# SLAVE.net
KiCad netlist of a schematic drawn in Altium Designer
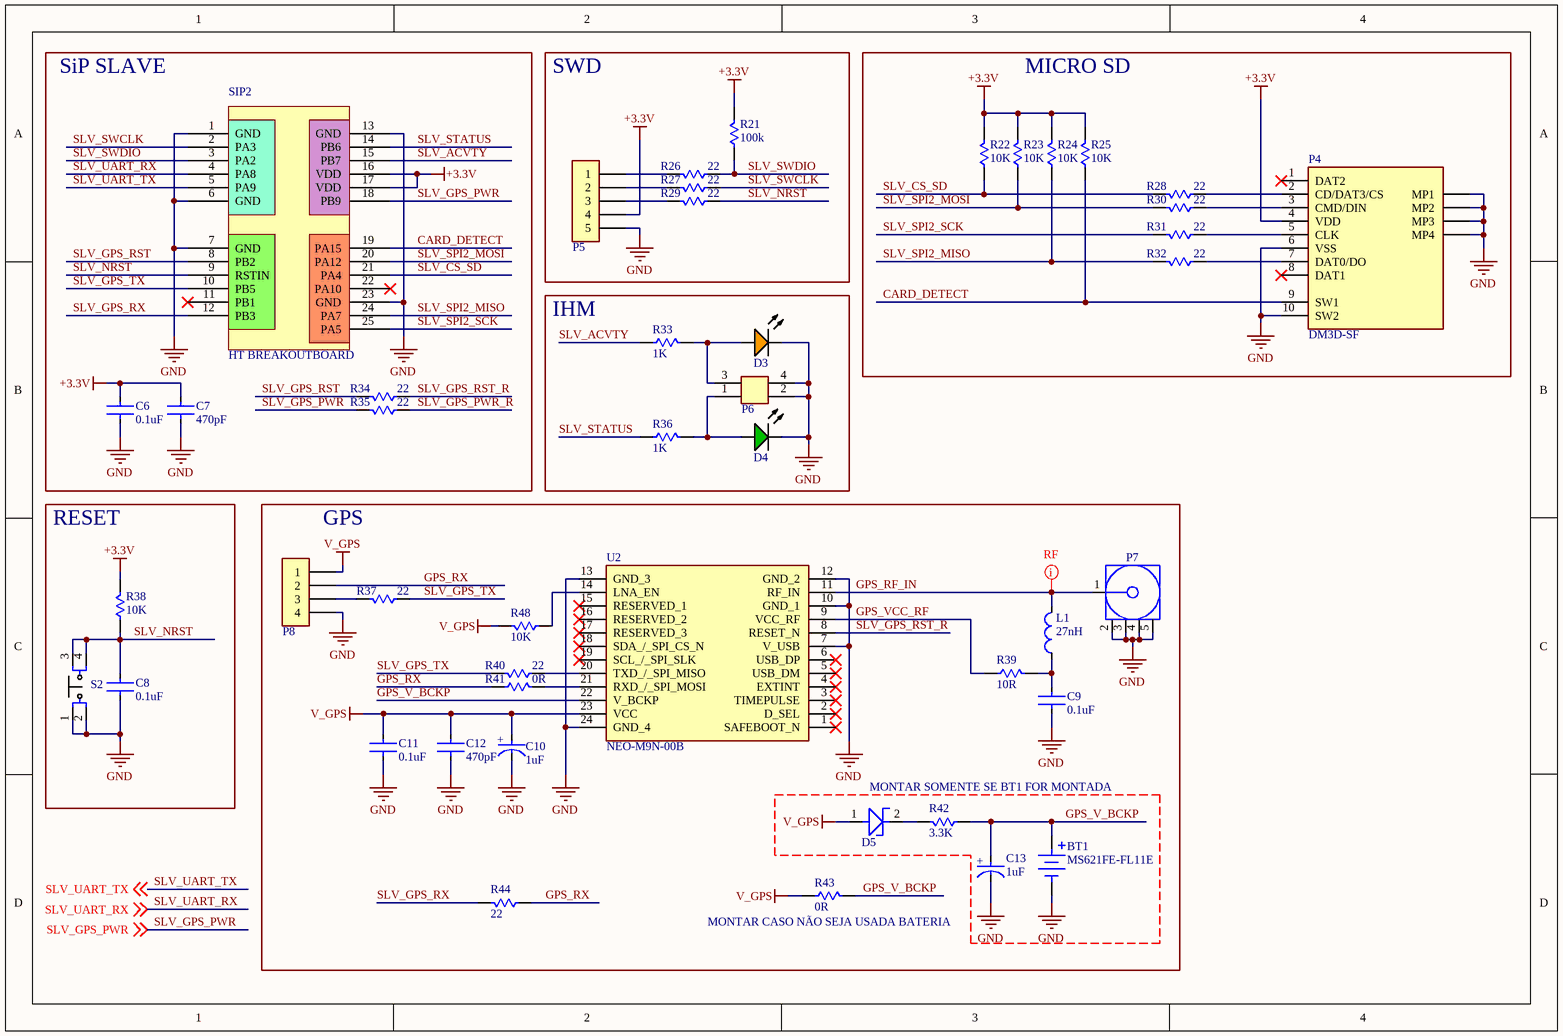
[diagram p0: SLAVE.SchDoc]

(export (version "E")
  (design (tool "Eeschema 10.0.6"))
  (components
    (comp (ref "BT1")
      (value "MS621FE-FL11E")
      (footprint "BAT_MS621FE-FL11E")
      (description "MS621FE-FL11E Coin Cell, Lithium, 5.5MAH, 3V Rechargeable Rohs")
      (fields (field (name "MANUFACTURER") "Seiko") (field (name "VOLTAGE") "3V"))
      (libsource (lib "Battery") (part "MS621FE-FL11E"))
    )
    (comp (ref "C6")
      (value "0.1uF")
      (footprint "0805-CAP")
      (description "CAP CER SMD 0805, 0.1uF / 16V, ±10%")
      (fields
        (field (name "MANUFACTURER") "Yageo")
        (field (name "MANUFACTURER PART NUMBER") "AC0805KRX7R7BB104")
      )
      (libsource (lib "Capacitor") (part "AC0805KRX7R7BB104"))
    )
    (comp (ref "C7")
      (value "470pF")
      (footprint "0805-CAP")
      (description "CAP CER SMD 0805, 470pF / 100V, ±5% C0G/NP0")
      (fields
        (field (name "MANUFACTURER") "Wurth Electronics")
        (field (name "MANUFACTURER PART NUMBER") "885012007086")
      )
      (libsource (lib "Capacitor") (part "885012007086"))
    )
    (comp (ref "C8")
      (value "0.1uF")
      (footprint "0805-CAP")
      (description "CAP CER SMD 0805, 0.1uF / 16V, ±10%")
      (fields
        (field (name "MANUFACTURER") "Yageo")
        (field (name "MANUFACTURER PART NUMBER") "AC0805KRX7R7BB104")
      )
      (libsource (lib "Capacitor") (part "AC0805KRX7R7BB104"))
    )
    (comp (ref "C9")
      (value "0.1uF")
      (footprint "0805-CAP")
      (description "CAP CER SMD 0805, 0.1uF / 16V, ±10%")
      (fields
        (field (name "MANUFACTURER") "Yageo")
        (field (name "MANUFACTURER PART NUMBER") "AC0805KRX7R7BB104")
      )
      (libsource (lib "Capacitor") (part "AC0805KRX7R7BB104"))
    )
    (comp (ref "C10")
      (value "1uF")
      (footprint "1206-CAP-TANT")
      (description "CAP TANT SMD 1206, 1uF / 20V, ±10%")
      (fields
        (field (name "MANUFACTURER") "Kyocera AVX")
        (field (name "MANUFACTURER PART NUMBER") "TAJA105K020RNJ")
      )
      (libsource (lib "Capacitor") (part "TAJA105K020RNJ"))
    )
    (comp (ref "C11")
      (value "0.1uF")
      (footprint "0805-CAP")
      (description "CAP CER SMD 0805, 0.1uF / 16V, ±10%")
      (fields
        (field (name "MANUFACTURER") "Yageo")
        (field (name "MANUFACTURER PART NUMBER") "AC0805KRX7R7BB104")
      )
      (libsource (lib "Capacitor") (part "AC0805KRX7R7BB104"))
    )
    (comp (ref "C12")
      (value "470pF")
      (footprint "0805-CAP")
      (description "CAP CER SMD 0805, 470pF / 100V, ±5% C0G/NP0")
      (fields
        (field (name "MANUFACTURER") "Wurth Electronics")
        (field (name "MANUFACTURER PART NUMBER") "885012007086")
      )
      (libsource (lib "Capacitor") (part "885012007086"))
    )
    (comp (ref "C13")
      (value "1uF")
      (footprint "1206-CAP-TANT")
      (description "CAP TANT SMD 1206, 1uF / 20V, ±10%")
      (fields
        (field (name "MANUFACTURER") "Kyocera AVX")
        (field (name "MANUFACTURER PART NUMBER") "TAJA105K020RNJ")
      )
      (libsource (lib "Capacitor") (part "TAJA105K020RNJ"))
    )
    (comp (ref "D3")
      (value "ORANGE")
      (footprint "0805-LED-ORANGE")
      (description "LED ORANGE, SMD 0805, 2.1V/30mA")
      (fields
        (field (name "MANUFACTURER") "Vishay Lite-On")
        (field (name "MANUFACTURER PART NUMBER") "LTST-C170AKT")
      )
      (libsource (lib "Diode") (part "LTST-C170AKT"))
    )
    (comp (ref "D4")
      (value "GREEN")
      (footprint "0805-LED-GREEN")
      (description "LED GREEN, SMD 0805, 2.1V/30mA")
      (fields
        (field (name "MANUFACTURER") "Vishay Lite-On")
        (field (name "MANUFACTURER PART NUMBER") "LTST-C170GKT")
      )
      (libsource (lib "Diode") (part "LTST-C170GKT"))
    )
    (comp (ref "D5")
      (value "NRVB120VLSFT1G")
      (footprint "SOD-123")
      (description "DIODE SHOTTKY SMD SOD-123F, 0,3V/1A, VBR 20V")
      (fields (field (name "MANUFACTURER") "ON Semiconductor"))
      (libsource (lib "Diode") (part "NRVB120VLSFT1G"))
    )
    (comp (ref "L1")
      (value "27nH")
      (footprint "PE-0603CD270JTT")
      (description "Inductor RF Chip Wirewound 27nH 5% 250MHz 35Q-Factor Ceramic 600mA 220mOhm DCR 0603 T/R")
      (fields
        (field (name "MANUFACTURER") "Pulse")
        (field (name "MANUFACTURER PART NUMBER") "PE-0603CD270JTT")
      )
      (libsource (lib "Inductor") (part "PE-0603CD270JTT"))
    )
    (comp (ref "P4")
      (value "DM3D-SF")
      (footprint "DM3DSF")
      (description "Memory Card Connectors MICRO SD CD CONN STD SMT PUSHPULL")
      (fields (field (name "MANUFACTURER") "Hirose"))
      (libsource (lib "Connector") (part "DM3D-SF"))
    )
    (comp (ref "P5")
      (value "Header 6")
      (footprint "_HEADER_5P_PVF")
      (fields
        (field (name "MANUFACTURER") "Amphenol ICC / FCI")
        (field (name "MANUFACTURER PART NUMBER") "75915-305LF")
      )
      (libsource (lib "Connector") (part "75915-305LF"))
    )
    (comp (ref "P6")
      (value "_HEADER_2X2_PVM_2.54MM")
      (footprint "67997-404HLF")
      (description "HEADER 2X3, PTH-2.54MM, VERT, MALE")
      (libsource (lib "Connector") (part "_HEADER_2X2_PVM_2.54MM"))
    )
    (comp (ref "P7")
      (value "CON-SMA-EDGE-S")
      (footprint "CON-SMA-EDGE-S")
      (description "Sma Female Connector, Pcb Edge Mount Rohs Compliant: Yes")
      (fields (field (name "MANUFACTURER") "RF Solutions"))
      (libsource (lib "Connector") (part "CON-SMA-EDGE-S"))
    )
    (comp (ref "P8")
      (value "NEO-5M-MODULE-WITHOUT-PPS")
      (footprint "NEO-5M-MODULE-NO-PPS")
      (description "NEO 5M GPS MODULE (NO PPS SIGNAL)")
      (libsource (lib "Connector") (part "NEO-5M-MODULE-WITHOUT-PPS"))
    )
    (comp (ref "R21")
      (value "100k")
      (footprint "0805-RES")
      (description "RES SMD 0805, 100K OHM 5% 1/8W")
      (fields
        (field (name "MANUFACTURER") "Panasonic")
        (field (name "MANUFACTURER PART NUMBER") "ERJ-6GEYJ104V")
      )
      (libsource (lib "Resistor") (part "ERJ-6GEYJ104V"))
    )
    (comp (ref "R22")
      (value "10K")
      (footprint "0805-RES")
      (description "Res Thin Film 0805 10K Ohm 1% 1/4W ±100ppm/°C Molded SMD Paper T/R")
      (fields
        (field (name "MANUFACTURER") "Stackpole Electronics")
        (field (name "MANUFACTURER PART NUMBER") "RNCP0805FTD10K0")
      )
      (libsource (lib "Resistor") (part "RNCP0805FTD10K0"))
    )
    (comp (ref "R23")
      (value "10K")
      (footprint "0805-RES")
      (description "Res Thin Film 0805 10K Ohm 1% 1/4W ±100ppm/°C Molded SMD Paper T/R")
      (fields
        (field (name "MANUFACTURER") "Stackpole Electronics")
        (field (name "MANUFACTURER PART NUMBER") "RNCP0805FTD10K0")
      )
      (libsource (lib "Resistor") (part "RNCP0805FTD10K0"))
    )
    (comp (ref "R24")
      (value "10K")
      (footprint "0805-RES")
      (description "Res Thin Film 0805 10K Ohm 1% 1/4W ±100ppm/°C Molded SMD Paper T/R")
      (fields
        (field (name "MANUFACTURER") "Stackpole Electronics")
        (field (name "MANUFACTURER PART NUMBER") "RNCP0805FTD10K0")
      )
      (libsource (lib "Resistor") (part "RNCP0805FTD10K0"))
    )
    (comp (ref "R25")
      (value "10K")
      (footprint "0805-RES")
      (description "Res Thin Film 0805 10K Ohm 1% 1/4W ±100ppm/°C Molded SMD Paper T/R")
      (fields
        (field (name "MANUFACTURER") "Stackpole Electronics")
        (field (name "MANUFACTURER PART NUMBER") "RNCP0805FTD10K0")
      )
      (libsource (lib "Resistor") (part "RNCP0805FTD10K0"))
    )
    (comp (ref "R26")
      (value "22")
      (footprint "0805-RES")
      (description "RES SMD 0805, 22 OHM 5% 1/4W")
      (fields
        (field (name "MANUFACTURER") "Panasonic")
        (field (name "MANUFACTURER PART NUMBER") "ERJ-P06J220V")
      )
      (libsource (lib "Resistor") (part "ERJ-P06J220V"))
    )
    (comp (ref "R27")
      (value "22")
      (footprint "0805-RES")
      (description "RES SMD 0805, 22 OHM 5% 1/4W")
      (fields
        (field (name "MANUFACTURER") "Panasonic")
        (field (name "MANUFACTURER PART NUMBER") "ERJ-P06J220V")
      )
      (libsource (lib "Resistor") (part "ERJ-P06J220V"))
    )
    (comp (ref "R28")
      (value "22")
      (footprint "0805-RES")
      (description "RES SMD 0805, 22 OHM 5% 1/4W")
      (fields
        (field (name "MANUFACTURER") "Panasonic")
        (field (name "MANUFACTURER PART NUMBER") "ERJ-P06J220V")
      )
      (libsource (lib "Resistor") (part "ERJ-P06J220V"))
    )
    (comp (ref "R29")
      (value "22")
      (footprint "0805-RES")
      (description "RES SMD 0805, 22 OHM 5% 1/4W")
      (fields
        (field (name "MANUFACTURER") "Panasonic")
        (field (name "MANUFACTURER PART NUMBER") "ERJ-P06J220V")
      )
      (libsource (lib "Resistor") (part "ERJ-P06J220V"))
    )
    (comp (ref "R30")
      (value "22")
      (footprint "0805-RES")
      (description "RES SMD 0805, 22 OHM 5% 1/4W")
      (fields
        (field (name "MANUFACTURER") "Panasonic")
        (field (name "MANUFACTURER PART NUMBER") "ERJ-P06J220V")
      )
      (libsource (lib "Resistor") (part "ERJ-P06J220V"))
    )
    (comp (ref "R31")
      (value "22")
      (footprint "0805-RES")
      (description "RES SMD 0805, 22 OHM 5% 1/4W")
      (fields
        (field (name "MANUFACTURER") "Panasonic")
        (field (name "MANUFACTURER PART NUMBER") "ERJ-P06J220V")
      )
      (libsource (lib "Resistor") (part "ERJ-P06J220V"))
    )
    (comp (ref "R32")
      (value "22")
      (footprint "0805-RES")
      (description "RES SMD 0805, 22 OHM 5% 1/4W")
      (fields
        (field (name "MANUFACTURER") "Panasonic")
        (field (name "MANUFACTURER PART NUMBER") "ERJ-P06J220V")
      )
      (libsource (lib "Resistor") (part "ERJ-P06J220V"))
    )
    (comp (ref "R33")
      (value "1K")
      (footprint "0805-RES")
      (description "Res Thin Film 0805 1K Ohm 1% 0.25W(1/4W) ±100ppm/C Sulfur Resistant Pad SMD T/R")
      (fields
        (field (name "MANUFACTURER") "Stackpole Electronics")
        (field (name "MANUFACTURER PART NUMBER") "RNCP0805FTD1K00")
      )
      (libsource (lib "Resistor") (part "RNCP0805FTD1K00"))
    )
    (comp (ref "R34")
      (value "22")
      (footprint "0805-RES")
      (description "RES SMD 0805, 22 OHM 5% 1/4W")
      (fields
        (field (name "MANUFACTURER") "Panasonic")
        (field (name "MANUFACTURER PART NUMBER") "ERJ-P06J220V")
      )
      (libsource (lib "Resistor") (part "ERJ-P06J220V"))
    )
    (comp (ref "R35")
      (value "22")
      (footprint "0805-RES")
      (description "RES SMD 0805, 22 OHM 5% 1/4W")
      (fields
        (field (name "MANUFACTURER") "Panasonic")
        (field (name "MANUFACTURER PART NUMBER") "ERJ-P06J220V")
      )
      (libsource (lib "Resistor") (part "ERJ-P06J220V"))
    )
    (comp (ref "R36")
      (value "1K")
      (footprint "0805-RES")
      (description "Res Thin Film 0805 1K Ohm 1% 0.25W(1/4W) ±100ppm/C Sulfur Resistant Pad SMD T/R")
      (fields
        (field (name "MANUFACTURER") "Stackpole Electronics")
        (field (name "MANUFACTURER PART NUMBER") "RNCP0805FTD1K00")
      )
      (libsource (lib "Resistor") (part "RNCP0805FTD1K00"))
    )
    (comp (ref "R37")
      (value "22")
      (footprint "0805-RES")
      (description "RES SMD 0805, 22 OHM 5% 1/4W")
      (fields
        (field (name "MANUFACTURER") "Panasonic")
        (field (name "MANUFACTURER PART NUMBER") "ERJ-P06J220V")
      )
      (libsource (lib "Resistor") (part "ERJ-P06J220V"))
    )
    (comp (ref "R38")
      (value "10K")
      (footprint "0805-RES")
      (description "Res Thin Film 0805 10K Ohm 1% 1/4W ±100ppm/°C Molded SMD Paper T/R")
      (fields
        (field (name "MANUFACTURER") "Stackpole Electronics")
        (field (name "MANUFACTURER PART NUMBER") "RNCP0805FTD10K0")
      )
      (libsource (lib "Resistor") (part "RNCP0805FTD10K0"))
    )
    (comp (ref "R39")
      (value "10R")
      (footprint "0805-RES")
      (description "RES SMD 0805, 10 OHM 1% 1/3W")
      (fields
        (field (name "MANUFACTURER") "Vishay")
        (field (name "MANUFACTURER PART NUMBER") "CRCW080510R0FKEAHP")
      )
      (libsource (lib "Resistor") (part "CRCW080510R0FKEAHP"))
    )
    (comp (ref "R40")
      (value "22")
      (footprint "0805-RES")
      (description "RES SMD 0805, 22 OHM 5% 1/4W")
      (fields
        (field (name "MANUFACTURER") "Panasonic")
        (field (name "MANUFACTURER PART NUMBER") "ERJ-P06J220V")
      )
      (libsource (lib "Resistor") (part "ERJ-P06J220V"))
    )
    (comp (ref "R41")
      (value "0R")
      (footprint "0805-RES")
      (description "RES SMD 0805, 0 OHM JUMPER 1/8W")
      (fields (field (name "TOLERANCE") "5%") (field (name "MANUFACTURER PART NUMBER") "RC0805JR-070RL"))
      (libsource (lib "Resistor") (part "RC0805JR-070RL"))
    )
    (comp (ref "R42")
      (value "3.3K")
      (footprint "0805-RES")
      (description "RES SMD 0805, 3.3K OHM 5% 0.4W")
      (fields (field (name "MANUFACTURER") "Rohm") (field (name "MANUFACTURER PART NUMBER") "ESR10EZPJ332"))
      (libsource (lib "Resistor") (part "ESR10EZPJ332"))
    )
    (comp (ref "R43")
      (value "0R")
      (footprint "0805-RES")
      (description "RES SMD 0805, 0 OHM JUMPER 1/8W")
      (fields (field (name "TOLERANCE") "5%") (field (name "MANUFACTURER PART NUMBER") "RC0805JR-070RL"))
      (libsource (lib "Resistor") (part "RC0805JR-070RL"))
    )
    (comp (ref "R44")
      (value "22")
      (footprint "0805-RES")
      (description "RES SMD 0805, 22 OHM 5% 1/4W")
      (fields
        (field (name "MANUFACTURER") "Panasonic")
        (field (name "MANUFACTURER PART NUMBER") "ERJ-P06J220V")
      )
      (libsource (lib "Resistor") (part "ERJ-P06J220V"))
    )
    (comp (ref "R48")
      (value "10K")
      (footprint "0805-RES")
      (description "Res Thin Film 0805 10K Ohm 1% 1/4W ±100ppm/°C Molded SMD Paper T/R")
      (fields
        (field (name "MANUFACTURER") "Stackpole Electronics")
        (field (name "MANUFACTURER PART NUMBER") "RNCP0805FTD10K0")
      )
      (libsource (lib "Resistor") (part "RNCP0805FTD10K0"))
    )
    (comp (ref "S2")
      (value "EVQ-P7A01P")
      (footprint "EVQP7A")
      (description "Switch Tactile N.O. SPST Rectangular Button Gull Wing 0.05A 12VDC 2.2N SMD Embossed T/R")
      (fields (field (name "MANUFACTURER") "Panasonic"))
      (libsource (lib "Switches") (part "EVQ-P7A01P"))
    )
    (comp (ref "SIP2")
      (value "HT BREAKOUTBOARD")
      (footprint "HT BREAKOUTBOARD PINS")
      (description "Pinos Fêmea para encaixe de HT Breakout")
      (libsource (lib "Connector") (part "HT BREAKOUTBOARD"))
    )
    (comp (ref "U2")
      (value "NEO-M9N-00B")
      (footprint "NEO-M9N-00B-MFG")
      (description "GNSS module, Flash, TCXO, SAW, LNA, LCC, 12x16 mm Professional Grade")
      (fields (field (name "MANUFACTURER") "u-blox"))
      (libsource (lib "IC") (part "NEO-M9N-00B"))
    )
  )
  (nets
    (net (code "1") (name "+3.3V") (class "Default")
      (node (ref "C6") (pin "1") (pinfunction "1_1") (pintype "passive"))
      (node (ref "C7") (pin "1") (pinfunction "1_1") (pintype "passive"))
      (node (ref "P4") (pin "4") (pinfunction "VDD_4") (pintype "passive"))
      (node (ref "P5") (pin "4") (pinfunction "4_4") (pintype "passive"))
      (node (ref "R21") (pin "2") (pinfunction "2_2") (pintype "passive"))
      (node (ref "R22") (pin "2") (pinfunction "2_2") (pintype "passive"))
      (node (ref "R23") (pin "2") (pinfunction "2_2") (pintype "passive"))
      (node (ref "R24") (pin "2") (pinfunction "2_2") (pintype "passive"))
      (node (ref "R25") (pin "2") (pinfunction "2_2") (pintype "passive"))
      (node (ref "R38") (pin "2") (pinfunction "2_2") (pintype "passive"))
      (node (ref "SIP2") (pin "16") (pinfunction "VDD_16") (pintype "passive"))
      (node (ref "SIP2") (pin "17") (pinfunction "VDD_17") (pintype "passive"))
    )
    (net (code "3") (name "/CARD_DETECT") (class "Default")
      (node (ref "P4") (pin "9") (pinfunction "SW1_9") (pintype "passive"))
      (node (ref "R25") (pin "1") (pinfunction "1_1") (pintype "passive"))
      (node (ref "SIP2") (pin "19") (pinfunction "PA15_19") (pintype "passive"))
    )
    (net (code "4") (name "/GPS_RF_IN") (class "Default")
      (node (ref "L1") (pin "2") (pinfunction "2_2") (pintype "passive"))
      (node (ref "P7") (pin "1") (pinfunction "SIGNAL_1") (pintype "passive"))
      (node (ref "U2") (pin "11") (pinfunction "RF_IN_11") (pintype "passive"))
    )
    (net (code "5") (name "/GPS_RX") (class "Default")
      (node (ref "P8") (pin "2") (pinfunction "2_2") (pintype "passive"))
      (node (ref "R41") (pin "1") (pinfunction "1_1") (pintype "passive"))
      (node (ref "R44") (pin "1") (pinfunction "1_1") (pintype "passive"))
    )
    (net (code "6") (name "/GPS_VCC_RF") (class "Default")
      (node (ref "R39") (pin "1") (pinfunction "1_1") (pintype "passive"))
      (node (ref "U2") (pin "9") (pinfunction "VCC_RF_9") (pintype "passive"))
    )
    (net (code "7") (name "/GPS_V_BCKP") (class "Default")
      (node (ref "BT1") (pin "POS") (pinfunction "POS_POS") (pintype "passive"))
      (node (ref "C13") (pin "1") (pinfunction "A_1") (pintype "passive"))
      (node (ref "R42") (pin "1") (pinfunction "1_1") (pintype "passive"))
      (node (ref "R43") (pin "2") (pinfunction "2_2") (pintype "passive"))
      (node (ref "U2") (pin "22") (pinfunction "V_BCKP_22") (pintype "passive"))
    )
    (net (code "8") (name "/SLV_ACVTY") (class "Default")
      (node (ref "R33") (pin "1") (pinfunction "1_1") (pintype "passive"))
      (node (ref "SIP2") (pin "15") (pinfunction "PB7_15") (pintype "passive"))
    )
    (net (code "9") (name "/SLV_CS_SD") (class "Default")
      (node (ref "R22") (pin "1") (pinfunction "1_1") (pintype "passive"))
      (node (ref "R28") (pin "2") (pinfunction "2_2") (pintype "passive"))
      (node (ref "SIP2") (pin "21") (pinfunction "PA4_21") (pintype "passive"))
    )
    (net (code "10") (name "/SLV_GPS_PWR_R") (class "Default")
      (node (ref "R35") (pin "1") (pinfunction "1_1") (pintype "passive"))
    )
    (net (code "11") (name "/SLV_GPS_RST") (class "Default")
      (node (ref "R34") (pin "2") (pinfunction "2_2") (pintype "passive"))
      (node (ref "SIP2") (pin "8") (pinfunction "PB2_8") (pintype "passive"))
    )
    (net (code "12") (name "/SLV_GPS_RST_R") (class "Default")
      (node (ref "R34") (pin "1") (pinfunction "1_1") (pintype "passive"))
      (node (ref "U2") (pin "8") (pinfunction "RESET_N_8") (pintype "passive"))
    )
    (net (code "13") (name "/SLV_GPS_RX") (class "Default")
      (node (ref "R44") (pin "2") (pinfunction "2_2") (pintype "passive"))
      (node (ref "SIP2") (pin "12") (pinfunction "PB3_12") (pintype "passive"))
    )
    (net (code "14") (name "/SLV_GPS_TX") (class "Default")
      (node (ref "R37") (pin "1") (pinfunction "1_1") (pintype "passive"))
      (node (ref "R40") (pin "2") (pinfunction "2_2") (pintype "passive"))
      (node (ref "SIP2") (pin "10") (pinfunction "PB5_10") (pintype "passive"))
    )
    (net (code "15") (name "/SLV_NRST") (class "Default")
      (node (ref "C8") (pin "1") (pinfunction "1_1") (pintype "passive"))
      (node (ref "R29") (pin "1") (pinfunction "1_1") (pintype "passive"))
      (node (ref "R38") (pin "1") (pinfunction "1_1") (pintype "passive"))
      (node (ref "S2") (pin "3") (pinfunction "3_3") (pintype "passive"))
      (node (ref "S2") (pin "4") (pinfunction "4_4") (pintype "passive"))
      (node (ref "SIP2") (pin "9") (pinfunction "RSTIN_9") (pintype "passive"))
    )
    (net (code "16") (name "/SLV_SPI2_MISO") (class "Default")
      (node (ref "R24") (pin "1") (pinfunction "1_1") (pintype "passive"))
      (node (ref "R32") (pin "2") (pinfunction "2_2") (pintype "passive"))
      (node (ref "SIP2") (pin "24") (pinfunction "PA7_24") (pintype "passive"))
    )
    (net (code "17") (name "/SLV_SPI2_MOSI") (class "Default")
      (node (ref "R23") (pin "1") (pinfunction "1_1") (pintype "passive"))
      (node (ref "R30") (pin "2") (pinfunction "2_2") (pintype "passive"))
      (node (ref "SIP2") (pin "20") (pinfunction "PA12_20") (pintype "passive"))
    )
    (net (code "18") (name "/SLV_SPI2_SCK") (class "Default")
      (node (ref "R31") (pin "2") (pinfunction "2_2") (pintype "passive"))
      (node (ref "SIP2") (pin "25") (pinfunction "PA5_25") (pintype "passive"))
    )
    (net (code "19") (name "/SLV_STATUS") (class "Default")
      (node (ref "R36") (pin "1") (pinfunction "1_1") (pintype "passive"))
      (node (ref "SIP2") (pin "14") (pinfunction "PB6_14") (pintype "passive"))
    )
    (net (code "20") (name "/SLV_SWCLK") (class "Default")
      (node (ref "R27") (pin "1") (pinfunction "1_1") (pintype "passive"))
      (node (ref "SIP2") (pin "2") (pinfunction "PA3_2") (pintype "passive"))
    )
    (net (code "21") (name "/SLV_SWDIO") (class "Default")
      (node (ref "R21") (pin "1") (pinfunction "1_1") (pintype "passive"))
      (node (ref "R26") (pin "1") (pinfunction "1_1") (pintype "passive"))
      (node (ref "SIP2") (pin "3") (pinfunction "PA2_3") (pintype "passive"))
    )
    (net (code "22") (name "GND") (class "Default")
      (node (ref "BT1") (pin "NEG") (pinfunction "NEG_NEG") (pintype "passive"))
      (node (ref "C10") (pin "2") (pinfunction "C_2") (pintype "passive"))
      (node (ref "C11") (pin "2") (pinfunction "2_2") (pintype "passive"))
      (node (ref "C12") (pin "2") (pinfunction "2_2") (pintype "passive"))
      (node (ref "C13") (pin "2") (pinfunction "C_2") (pintype "passive"))
      (node (ref "C6") (pin "2") (pinfunction "2_2") (pintype "passive"))
      (node (ref "C7") (pin "2") (pinfunction "2_2") (pintype "passive"))
      (node (ref "C8") (pin "2") (pinfunction "2_2") (pintype "passive"))
      (node (ref "C9") (pin "1") (pinfunction "1_1") (pintype "passive"))
      (node (ref "D3") (pin "2") (pinfunction "K_2") (pintype "passive"))
      (node (ref "D4") (pin "2") (pinfunction "K_2") (pintype "passive"))
      (node (ref "P4") (pin "10") (pinfunction "SW2_10") (pintype "passive"))
      (node (ref "P4") (pin "6") (pinfunction "VSS_6") (pintype "passive"))
      (node (ref "P4") (pin "MP1") (pinfunction "MP1_MP1") (pintype "passive"))
      (node (ref "P4") (pin "MP2") (pinfunction "MP2_MP2") (pintype "passive"))
      (node (ref "P4") (pin "MP3") (pinfunction "MP3_MP3") (pintype "passive"))
      (node (ref "P4") (pin "MP4") (pinfunction "MP4_MP4") (pintype "passive"))
      (node (ref "P5") (pin "5") (pinfunction "5_5") (pintype "passive"))
      (node (ref "P6") (pin "2") (pinfunction "2_2") (pintype "passive"))
      (node (ref "P6") (pin "4") (pinfunction "4_4") (pintype "passive"))
      (node (ref "P7") (pin "2") (pinfunction "GND1_2") (pintype "power_in"))
      (node (ref "P7") (pin "3") (pinfunction "GND2_3") (pintype "power_in"))
      (node (ref "P7") (pin "4") (pinfunction "GND3_4") (pintype "power_in"))
      (node (ref "P7") (pin "5") (pinfunction "GND4_5") (pintype "power_in"))
      (node (ref "P8") (pin "4") (pinfunction "4_4") (pintype "passive"))
      (node (ref "S2") (pin "1") (pinfunction "1_1") (pintype "passive"))
      (node (ref "S2") (pin "2") (pinfunction "2_2") (pintype "passive"))
      (node (ref "SIP2") (pin "1") (pinfunction "GND_1") (pintype "passive"))
      (node (ref "SIP2") (pin "13") (pinfunction "GND_13") (pintype "passive"))
      (node (ref "SIP2") (pin "23") (pinfunction "GND_23") (pintype "passive"))
      (node (ref "SIP2") (pin "6") (pinfunction "GND_6") (pintype "passive"))
      (node (ref "SIP2") (pin "7") (pinfunction "GND_7") (pintype "passive"))
      (node (ref "U2") (pin "10") (pinfunction "GND_1_10") (pintype "passive"))
      (node (ref "U2") (pin "12") (pinfunction "GND_2_12") (pintype "passive"))
      (node (ref "U2") (pin "13") (pinfunction "GND_3_13") (pintype "passive"))
      (node (ref "U2") (pin "24") (pinfunction "GND_4_24") (pintype "passive"))
      (node (ref "U2") (pin "7") (pinfunction "V_USB_7") (pintype "passive"))
    )
    (net (code "23") (name "Net-(C9-Pad2)") (class "Default")
      (node (ref "C9") (pin "2") (pinfunction "2_2") (pintype "passive"))
      (node (ref "L1") (pin "1") (pinfunction "1_1") (pintype "passive"))
      (node (ref "R39") (pin "2") (pinfunction "2_2") (pintype "passive"))
    )
    (net (code "24") (name "Net-(D3-A)") (class "Default")
      (node (ref "D3") (pin "1") (pinfunction "A_1") (pintype "passive"))
      (node (ref "P6") (pin "3") (pinfunction "3_3") (pintype "passive"))
      (node (ref "R33") (pin "2") (pinfunction "2_2") (pintype "passive"))
    )
    (net (code "25") (name "Net-(D4-A)") (class "Default")
      (node (ref "D4") (pin "1") (pinfunction "A_1") (pintype "passive"))
      (node (ref "P6") (pin "1") (pinfunction "1_1") (pintype "passive"))
      (node (ref "R36") (pin "2") (pinfunction "2_2") (pintype "passive"))
    )
    (net (code "26") (name "Net-(D5-Pad2)") (class "Default")
      (node (ref "D5") (pin "2") (pinfunction "2_2") (pintype "passive"))
      (node (ref "R42") (pin "2") (pinfunction "2_2") (pintype "passive"))
    )
    (net (code "27") (name "Net-(P4-CD{slash}DAT3{slash}CS)") (class "Default")
      (node (ref "P4") (pin "2") (pinfunction "CD/DAT3/CS_2") (pintype "passive"))
      (node (ref "R28") (pin "1") (pinfunction "1_1") (pintype "passive"))
    )
    (net (code "28") (name "Net-(P4-CLK)") (class "Default")
      (node (ref "P4") (pin "5") (pinfunction "CLK_5") (pintype "passive"))
      (node (ref "R31") (pin "1") (pinfunction "1_1") (pintype "passive"))
    )
    (net (code "29") (name "Net-(P4-CMD{slash}DIN)") (class "Default")
      (node (ref "P4") (pin "3") (pinfunction "CMD/DIN_3") (pintype "passive"))
      (node (ref "R30") (pin "1") (pinfunction "1_1") (pintype "passive"))
    )
    (net (code "30") (name "Net-(P4-DAT0{slash}DO)") (class "Default")
      (node (ref "P4") (pin "7") (pinfunction "DAT0/DO_7") (pintype "passive"))
      (node (ref "R32") (pin "1") (pinfunction "1_1") (pintype "passive"))
    )
    (net (code "31") (name "Net-(P5-Pad1)") (class "Default")
      (node (ref "P5") (pin "1") (pinfunction "1_1") (pintype "passive"))
      (node (ref "R26") (pin "2") (pinfunction "2_2") (pintype "passive"))
    )
    (net (code "32") (name "Net-(P5-Pad2)") (class "Default")
      (node (ref "P5") (pin "2") (pinfunction "2_2") (pintype "passive"))
      (node (ref "R27") (pin "2") (pinfunction "2_2") (pintype "passive"))
    )
    (net (code "33") (name "Net-(P5-Pad3)") (class "Default")
      (node (ref "P5") (pin "3") (pinfunction "3_3") (pintype "passive"))
      (node (ref "R29") (pin "2") (pinfunction "2_2") (pintype "passive"))
    )
    (net (code "34") (name "Net-(P8-Pad3)") (class "Default")
      (node (ref "P8") (pin "3") (pinfunction "3_3") (pintype "passive"))
      (node (ref "R37") (pin "2") (pinfunction "2_2") (pintype "passive"))
    )
    (net (code "35") (name "Net-(U2-LNA_EN)") (class "Default")
      (node (ref "R48") (pin "1") (pinfunction "1_1") (pintype "passive"))
      (node (ref "U2") (pin "14") (pinfunction "LNA_EN_14") (pintype "passive"))
    )
    (net (code "36") (name "Net-(U2-RXD_{slash}_SPI_MOSI)") (class "Default")
      (node (ref "R41") (pin "2") (pinfunction "2_2") (pintype "passive"))
      (node (ref "U2") (pin "21") (pinfunction "RXD_/_SPI_MOSI_21") (pintype "passive"))
    )
    (net (code "37") (name "Net-(U2-TXD_{slash}_SPI_MISO)") (class "Default")
      (node (ref "R40") (pin "1") (pinfunction "1_1") (pintype "passive"))
      (node (ref "U2") (pin "20") (pinfunction "TXD_/_SPI_MISO_20") (pintype "passive"))
    )
    (net (code "38") (name "SLV_GPS_PWR") (class "Default")
      (node (ref "R35") (pin "2") (pinfunction "2_2") (pintype "passive"))
      (node (ref "SIP2") (pin "18") (pinfunction "PB9_18") (pintype "passive"))
    )
    (net (code "39") (name "SLV_UART_RX") (class "Default")
      (node (ref "SIP2") (pin "4") (pinfunction "PA8_4") (pintype "passive"))
    )
    (net (code "40") (name "SLV_UART_TX") (class "Default")
      (node (ref "SIP2") (pin "5") (pinfunction "PA9_5") (pintype "passive"))
    )
    (net (code "41") (name "V_GPS") (class "Default")
      (node (ref "C10") (pin "1") (pinfunction "A_1") (pintype "passive"))
      (node (ref "C11") (pin "1") (pinfunction "1_1") (pintype "passive"))
      (node (ref "C12") (pin "1") (pinfunction "1_1") (pintype "passive"))
      (node (ref "D5") (pin "1") (pinfunction "1_1") (pintype "passive"))
      (node (ref "P8") (pin "1") (pinfunction "1_1") (pintype "passive"))
      (node (ref "R43") (pin "1") (pinfunction "1_1") (pintype "passive"))
      (node (ref "R48") (pin "2") (pinfunction "2_2") (pintype "passive"))
      (node (ref "U2") (pin "23") (pinfunction "VCC_23") (pintype "passive"))
    )
    (net (code "42") (name "unconnected-(P4-DAT1-Pad8)") (class "Default")
      (node (ref "P4") (pin "8") (pinfunction "DAT1_8") (pintype "passive+no_connect"))
    )
    (net (code "43") (name "unconnected-(P4-DAT2-Pad1)") (class "Default")
      (node (ref "P4") (pin "1") (pinfunction "DAT2_1") (pintype "passive+no_connect"))
    )
    (net (code "44") (name "unconnected-(SIP2-PA10-Pad22)") (class "Default")
      (node (ref "SIP2") (pin "22") (pinfunction "PA10_22") (pintype "passive+no_connect"))
    )
    (net (code "45") (name "unconnected-(SIP2-PB1-Pad11)") (class "Default")
      (node (ref "SIP2") (pin "11") (pinfunction "PB1_11") (pintype "passive+no_connect"))
    )
    (net (code "46") (name "unconnected-(U2-D_SEL-Pad2)") (class "Default")
      (node (ref "U2") (pin "2") (pinfunction "D_SEL_2") (pintype "passive+no_connect"))
    )
    (net (code "47") (name "unconnected-(U2-EXTINT-Pad4)") (class "Default")
      (node (ref "U2") (pin "4") (pinfunction "EXTINT_4") (pintype "passive+no_connect"))
    )
    (net (code "48") (name "unconnected-(U2-RESERVED_1-Pad15)") (class "Default")
      (node (ref "U2") (pin "15") (pinfunction "RESERVED_1_15") (pintype "passive+no_connect"))
    )
    (net (code "49") (name "unconnected-(U2-RESERVED_2-Pad16)") (class "Default")
      (node (ref "U2") (pin "16") (pinfunction "RESERVED_2_16") (pintype "passive+no_connect"))
    )
    (net (code "50") (name "unconnected-(U2-RESERVED_3-Pad17)") (class "Default")
      (node (ref "U2") (pin "17") (pinfunction "RESERVED_3_17") (pintype "passive+no_connect"))
    )
    (net (code "51") (name "unconnected-(U2-SAFEBOOT_N-Pad1)") (class "Default")
      (node (ref "U2") (pin "1") (pinfunction "SAFEBOOT_N_1") (pintype "passive+no_connect"))
    )
    (net (code "52") (name "unconnected-(U2-SCL_{slash}_SPI_SLK-Pad19)") (class "Default")
      (node (ref "U2") (pin "19") (pinfunction "SCL_/_SPI_SLK_19") (pintype "passive+no_connect"))
    )
    (net (code "53") (name "unconnected-(U2-SDA_{slash}_SPI_CS_N-Pad18)") (class "Default")
      (node (ref "U2") (pin "18") (pinfunction "SDA_/_SPI_CS_N_18") (pintype "passive+no_connect"))
    )
    (net (code "54") (name "unconnected-(U2-TIMEPULSE-Pad3)") (class "Default")
      (node (ref "U2") (pin "3") (pinfunction "TIMEPULSE_3") (pintype "passive+no_connect"))
    )
    (net (code "55") (name "unconnected-(U2-USB_DM-Pad5)") (class "Default")
      (node (ref "U2") (pin "5") (pinfunction "USB_DM_5") (pintype "passive+no_connect"))
    )
    (net (code "56") (name "unconnected-(U2-USB_DP-Pad6)") (class "Default")
      (node (ref "U2") (pin "6") (pinfunction "USB_DP_6") (pintype "passive+no_connect"))
    )
  )
)
